# Schema_GEVE.net
KiCad netlist of a schematic drawn in Altium Designer
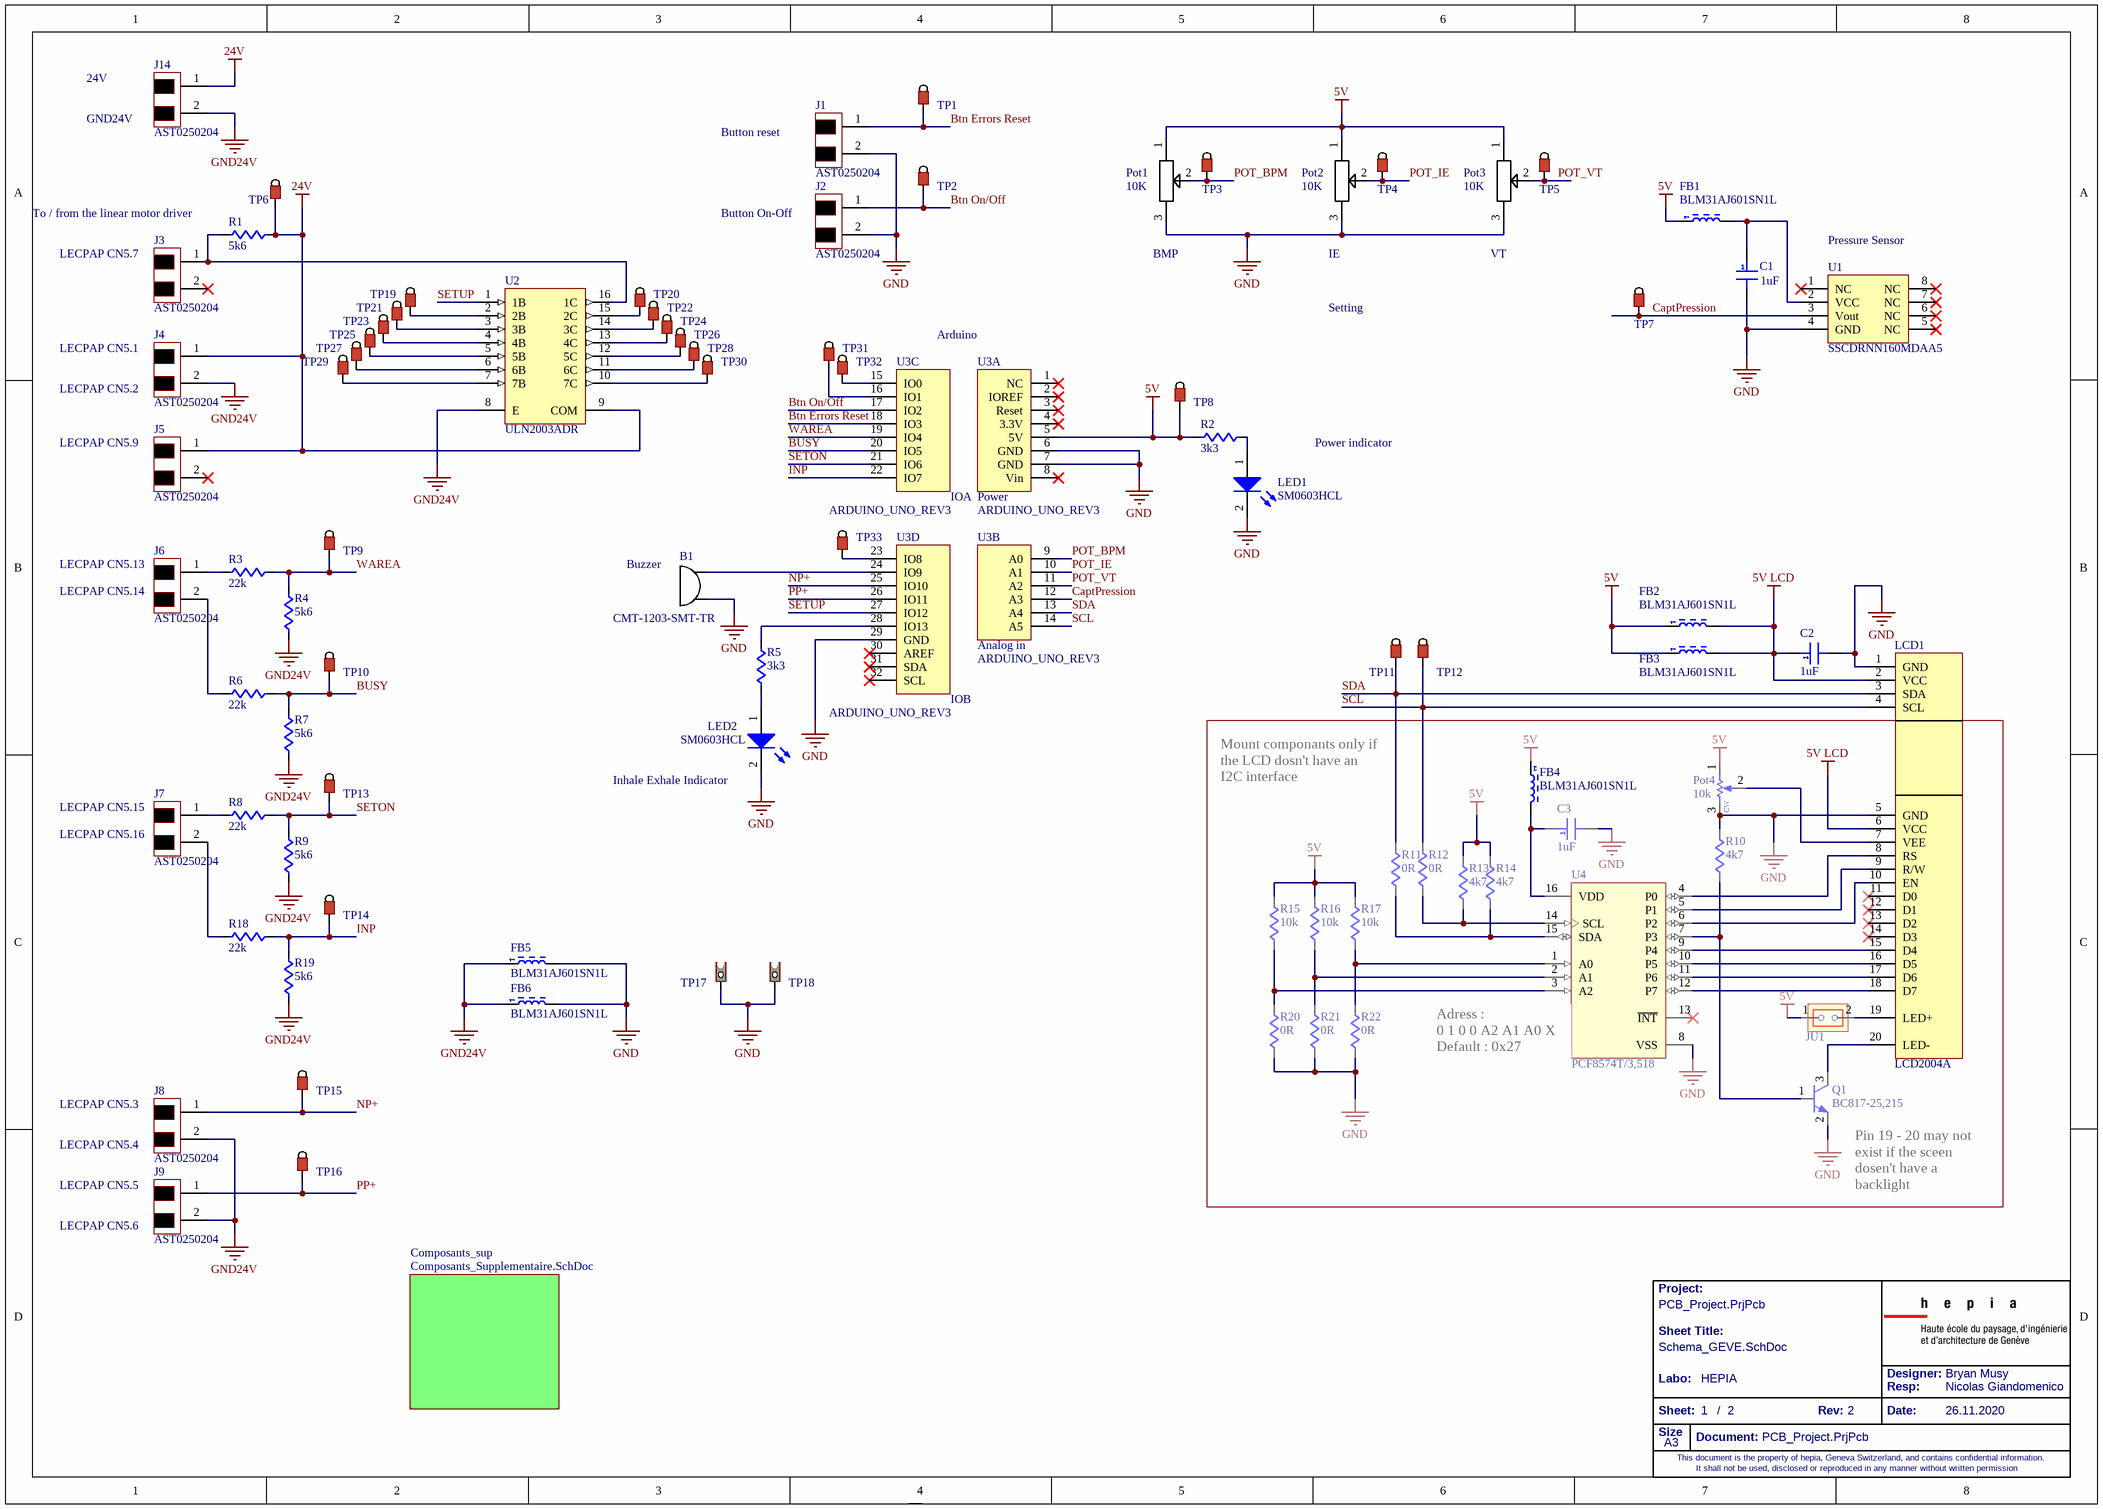
[diagram p0: Schema_GEVE.SchDoc]

(export (version "E")
  (design (tool "Eeschema 10.0.6"))
  (components
    (comp (ref "B1")
      (value "CMT-1203-SMT-TR")
      (footprint "CMT-1203-SMT-TR")
      (fields (field (name "MANUFACTURER") "CUI Devices") (field (name "DESIGNER") "B.Musy"))
      (libsource (lib "GEVE_lib") (part "CMT-1203-SMT-TR"))
    )
    (comp (ref "C1")
      (value "1uF")
      (footprint "CAP_0603H0.8")
      (description "Boite Labo 0603: Ceramic Cap, 1uF, 10%, 50V, CAP_0603H0.8")
      (fields
        (field (name "PART NUMBER") "D_CAP-64")
        (field (name "MANUFACTURER") "Murata")
        (field (name "DESIGNER") "R.Mastrocola")
      )
      (libsource (lib "Database_Altium_Hepia_Elec") (part "Cap"))
    )
    (comp (ref "C2")
      (value "1uF")
      (footprint "CAP_0603H0.8")
      (description "Boite Labo 0603: Ceramic Cap, 1uF, 10%, 50V, CAP_0603H0.8")
      (fields
        (field (name "PART NUMBER") "D_CAP-64")
        (field (name "MANUFACTURER") "Murata")
        (field (name "DESIGNER") "R.Mastrocola")
      )
      (libsource (lib "Database_Altium_Hepia_Elec") (part "Cap"))
    )
    (comp (ref "C3")
      (value "1uF")
      (footprint "CAP_0603H0.8")
      (description "Boite Labo 0603: Ceramic Cap, 1uF, 10%, 50V, CAP_0603H0.8")
      (fields
        (field (name "PART NUMBER") "D_CAP-64")
        (field (name "MANUFACTURER") "Murata")
        (field (name "DESIGNER") "R.Mastrocola")
      )
      (libsource (lib "Database_Altium_Hepia_Elec") (part "Cap"))
    )
    (comp (ref "FB1")
      (value "BLM31AJ601SN1L")
      (footprint "FERRITE_1206_1.1")
      (description "Chip Ferrite Bead, 1206, 200mA, DCRes=0.90ohm, 100MHz_Res=600ohm")
      (fields
        (field (name "PART NUMBER") "D_IND-1")
        (field (name "MANUFACTURER") "Murata")
        (field (name "DESIGNER") "FG")
      )
      (libsource (lib "Database_Altium_Hepia_Elec") (part "Ferrite"))
    )
    (comp (ref "FB2")
      (value "BLM31AJ601SN1L")
      (footprint "FERRITE_1206_1.1")
      (description "Chip Ferrite Bead, 1206, 200mA, DCRes=0.90ohm, 100MHz_Res=600ohm")
      (fields
        (field (name "PART NUMBER") "D_IND-1")
        (field (name "MANUFACTURER") "Murata")
        (field (name "DESIGNER") "FG")
      )
      (libsource (lib "Database_Altium_Hepia_Elec") (part "Ferrite"))
    )
    (comp (ref "FB3")
      (value "BLM31AJ601SN1L")
      (footprint "FERRITE_1206_1.1")
      (description "Chip Ferrite Bead, 1206, 200mA, DCRes=0.90ohm, 100MHz_Res=600ohm")
      (fields
        (field (name "PART NUMBER") "D_IND-1")
        (field (name "MANUFACTURER") "Murata")
        (field (name "DESIGNER") "FG")
      )
      (libsource (lib "Database_Altium_Hepia_Elec") (part "Ferrite"))
    )
    (comp (ref "FB4")
      (value "BLM31AJ601SN1L")
      (footprint "FERRITE_1206_1.1")
      (description "Chip Ferrite Bead, 1206, 200mA, DCRes=0.90ohm, 100MHz_Res=600ohm")
      (fields
        (field (name "PART NUMBER") "D_IND-1")
        (field (name "MANUFACTURER") "Murata")
        (field (name "DESIGNER") "FG")
      )
      (libsource (lib "Database_Altium_Hepia_Elec") (part "Ferrite"))
    )
    (comp (ref "FB5")
      (value "BLM31AJ601SN1L")
      (footprint "FERRITE_1206_1.1")
      (description "Chip Ferrite Bead, 1206, 200mA, DCRes=0.90ohm, 100MHz_Res=600ohm")
      (fields
        (field (name "PART NUMBER") "D_IND-1")
        (field (name "MANUFACTURER") "Murata")
        (field (name "DESIGNER") "FG")
      )
      (libsource (lib "Database_Altium_Hepia_Elec") (part "Ferrite"))
    )
    (comp (ref "FB6")
      (value "BLM31AJ601SN1L")
      (footprint "FERRITE_1206_1.1")
      (description "Chip Ferrite Bead, 1206, 200mA, DCRes=0.90ohm, 100MHz_Res=600ohm")
      (fields
        (field (name "PART NUMBER") "D_IND-1")
        (field (name "MANUFACTURER") "Murata")
        (field (name "DESIGNER") "FG")
      )
      (libsource (lib "Database_Altium_Hepia_Elec") (part "Ferrite"))
    )
    (comp (ref "J1")
      (value "AST0250204")
      (footprint "AST0250204")
      (fields (field (name "MANUFACTURER") "METZ Connect USA") (field (name "DESIGNER") "B.Musy"))
      (libsource (lib "GEVE_lib") (part "AST0250204"))
    )
    (comp (ref "J2")
      (value "AST0250204")
      (footprint "AST0250204")
      (fields (field (name "MANUFACTURER") "METZ Connect USA") (field (name "DESIGNER") "B.Musy"))
      (libsource (lib "GEVE_lib") (part "AST0250204"))
    )
    (comp (ref "J3")
      (value "AST0250204")
      (footprint "AST0250204")
      (fields (field (name "MANUFACTURER") "METZ Connect USA") (field (name "DESIGNER") "B.Musy"))
      (libsource (lib "GEVE_lib") (part "AST0250204"))
    )
    (comp (ref "J4")
      (value "AST0250204")
      (footprint "AST0250204")
      (fields (field (name "MANUFACTURER") "METZ Connect USA") (field (name "DESIGNER") "B.Musy"))
      (libsource (lib "GEVE_lib") (part "AST0250204"))
    )
    (comp (ref "J5")
      (value "AST0250204")
      (footprint "AST0250204")
      (fields (field (name "MANUFACTURER") "METZ Connect USA") (field (name "DESIGNER") "B.Musy"))
      (libsource (lib "GEVE_lib") (part "AST0250204"))
    )
    (comp (ref "J6")
      (value "AST0250204")
      (footprint "AST0250204")
      (fields (field (name "MANUFACTURER") "METZ Connect USA") (field (name "DESIGNER") "B.Musy"))
      (libsource (lib "GEVE_lib") (part "AST0250204"))
    )
    (comp (ref "J7")
      (value "AST0250204")
      (footprint "AST0250204")
      (fields (field (name "MANUFACTURER") "METZ Connect USA") (field (name "DESIGNER") "B.Musy"))
      (libsource (lib "GEVE_lib") (part "AST0250204"))
    )
    (comp (ref "J8")
      (value "AST0250204")
      (footprint "AST0250204")
      (fields (field (name "MANUFACTURER") "METZ Connect USA") (field (name "DESIGNER") "B.Musy"))
      (libsource (lib "GEVE_lib") (part "AST0250204"))
    )
    (comp (ref "J9")
      (value "AST0250204")
      (footprint "AST0250204")
      (fields (field (name "MANUFACTURER") "METZ Connect USA") (field (name "DESIGNER") "B.Musy"))
      (libsource (lib "GEVE_lib") (part "AST0250204"))
    )
    (comp (ref "J14")
      (value "AST0250204")
      (footprint "AST0250204")
      (description "Connecteur a levier")
      (fields (field (name "MANUFACTURER") "METZ Connect USA") (field (name "DESIGNER") "B.Musy"))
      (libsource (lib "GEVE_lib") (part "AST0250204"))
    )
    (comp (ref "JU1")
      (value "PREC002SAAN-RC")
      (footprint "Jumper_2P_P2.54")
      (description "CONN HEADER .100\" SNGL STR 2POS")
      (fields
        (field (name "PART NUMBER") "M_EME-2")
        (field (name "MANUFACTURER") "Sullins Connector Solutions")
        (field (name "DESIGNER") "R.Mastrocola")
      )
      (libsource (lib "Database_Altium_Hepia_Elec") (part "Jumper 2"))
    )
    (comp (ref "LCD1")
      (value "LCD2004A")
      (footprint "LCD2004")
      (fields (field (name "MANUFACTURER") "Geekcreit") (field (name "DESIGNER") "B.Musy"))
      (libsource (lib "GEVE_lib") (part "LCD2004A"))
    )
    (comp (ref "LED1")
      (value "SM0603HCL")
      (footprint "LED_0603-12")
      (description "LED red smd 0603 2 mA")
      (fields
        (field (name "PART NUMBER") "D_OPT-2")
        (field (name "MANUFACTURER") "Bivar")
        (field (name "DESIGNER") "FG")
      )
      (libsource (lib "Database_Altium_Hepia_Elec") (part "LED-12"))
    )
    (comp (ref "LED2")
      (value "SM0603HCL")
      (footprint "LED_0603-12")
      (description "LED red smd 0603 2 mA")
      (fields
        (field (name "PART NUMBER") "D_OPT-2")
        (field (name "MANUFACTURER") "Bivar")
        (field (name "DESIGNER") "FG")
      )
      (libsource (lib "Database_Altium_Hepia_Elec") (part "LED-12"))
    )
    (comp (ref "Pot1")
      (value "10K")
      (footprint "PCW1J-B28-BAB103L")
      (fields (field (name "MANUFACTURER") "Bourns.inc") (field (name "DESIGNER") "B.Musy"))
      (libsource (lib "GEVE_lib") (part "POT10K"))
    )
    (comp (ref "Pot2")
      (value "10K")
      (footprint "PCW1J-B28-BAB103L")
      (fields (field (name "MANUFACTURER") "Bourns.inc") (field (name "DESIGNER") "B.Musy"))
      (libsource (lib "GEVE_lib") (part "POT10K"))
    )
    (comp (ref "Pot3")
      (value "10K")
      (footprint "PCW1J-B28-BAB103L")
      (fields (field (name "MANUFACTURER") "Bourns.inc") (field (name "DESIGNER") "B.Musy"))
      (libsource (lib "GEVE_lib") (part "POT10K"))
    )
    (comp (ref "Pot4")
      (value "10k")
      (footprint "Trimpot-3313-J1")
      (description "TrimPot SMD 1 Tour 10k 3mm")
      (fields
        (field (name "PART NUMBER") "D_RES-331")
        (field (name "MANUFACTURER") "Bourns")
        (field (name "DESIGNER") "JCO")
      )
      (libsource (lib "Database_Altium_Hepia_Elec") (part "Trimmer"))
    )
    (comp (ref "Q1")
      (value "BC817-25,215")
      (footprint "SOT23-3")
      (description "Bipolar NPN, General Purpose, 45V,100MHz, 500mA")
      (fields
        (field (name "PART NUMBER") "D_TRS-9")
        (field (name "MANUFACTURER") "NXP Semi")
        (field (name "DESIGNER") "R.Mastrocola")
      )
      (libsource (lib "Database_Altium_Hepia_Elec") (part "NPN_1"))
    )
    (comp (ref "R1")
      (value "5k6")
      (footprint "RES_0603")
      (description "Thin Film Resistor, Boite Labo 0603, 5k6 1%")
      (fields
        (field (name "PART NUMBER") "D_RES-92")
        (field (name "MANUFACTURER") "Vishay")
        (field (name "DESIGNER") "R.Mastrocola")
      )
      (libsource (lib "Database_Altium_Hepia_Elec") (part "RESISTOR"))
    )
    (comp (ref "R2")
      (value "3k3")
      (footprint "RES_0603")
      (description "Thin Film Resistor, Boite Labo 0603, 3k3 1%")
      (fields
        (field (name "PART NUMBER") "D_RES-86")
        (field (name "MANUFACTURER") "Vishay")
        (field (name "DESIGNER") "R.Mastrocola")
      )
      (libsource (lib "Database_Altium_Hepia_Elec") (part "RESISTOR"))
    )
    (comp (ref "R3")
      (value "22k")
      (footprint "RES_0603")
      (description "Thin Film Resistor, Boite Labo 0603, 22k 1%")
      (fields
        (field (name "PART NUMBER") "D_RES-106")
        (field (name "MANUFACTURER") "Vishay")
        (field (name "DESIGNER") "R.Mastrocola")
      )
      (libsource (lib "Database_Altium_Hepia_Elec") (part "RESISTOR"))
    )
    (comp (ref "R4")
      (value "5k6")
      (footprint "RES_0603")
      (description "Thin Film Resistor, Boite Labo 0603, 5k6 1%")
      (fields
        (field (name "PART NUMBER") "D_RES-92")
        (field (name "MANUFACTURER") "Vishay")
        (field (name "DESIGNER") "R.Mastrocola")
      )
      (libsource (lib "Database_Altium_Hepia_Elec") (part "RESISTOR"))
    )
    (comp (ref "R5")
      (value "3k3")
      (footprint "RES_0603")
      (description "Thin Film Resistor, Boite Labo 0603, 3k3 1%")
      (fields
        (field (name "PART NUMBER") "D_RES-86")
        (field (name "MANUFACTURER") "Vishay")
        (field (name "DESIGNER") "R.Mastrocola")
      )
      (libsource (lib "Database_Altium_Hepia_Elec") (part "RESISTOR"))
    )
    (comp (ref "R6")
      (value "22k")
      (footprint "RES_0603")
      (description "Thin Film Resistor, Boite Labo 0603, 22k 1%")
      (fields
        (field (name "PART NUMBER") "D_RES-106")
        (field (name "MANUFACTURER") "Vishay")
        (field (name "DESIGNER") "R.Mastrocola")
      )
      (libsource (lib "Database_Altium_Hepia_Elec") (part "RESISTOR"))
    )
    (comp (ref "R7")
      (value "5k6")
      (footprint "RES_0603")
      (description "Thin Film Resistor, Boite Labo 0603, 5k6 1%")
      (fields
        (field (name "PART NUMBER") "D_RES-92")
        (field (name "MANUFACTURER") "Vishay")
        (field (name "DESIGNER") "R.Mastrocola")
      )
      (libsource (lib "Database_Altium_Hepia_Elec") (part "RESISTOR"))
    )
    (comp (ref "R8")
      (value "22k")
      (footprint "RES_0603")
      (description "Thin Film Resistor, Boite Labo 0603, 22k 1%")
      (fields
        (field (name "PART NUMBER") "D_RES-106")
        (field (name "MANUFACTURER") "Vishay")
        (field (name "DESIGNER") "R.Mastrocola")
      )
      (libsource (lib "Database_Altium_Hepia_Elec") (part "RESISTOR"))
    )
    (comp (ref "R9")
      (value "5k6")
      (footprint "RES_0603")
      (description "Thin Film Resistor, Boite Labo 0603, 5k6 1%")
      (fields
        (field (name "PART NUMBER") "D_RES-92")
        (field (name "MANUFACTURER") "Vishay")
        (field (name "DESIGNER") "R.Mastrocola")
      )
      (libsource (lib "Database_Altium_Hepia_Elec") (part "RESISTOR"))
    )
    (comp (ref "R10")
      (value "4k7")
      (footprint "RES_0603")
      (description "Thin Film Resistor, Boite Labo 0603, 4k7 1%")
      (fields
        (field (name "PART NUMBER") "D_RES-90")
        (field (name "MANUFACTURER") "Vishay")
        (field (name "DESIGNER") "R.Mastrocola")
      )
      (libsource (lib "Database_Altium_Hepia_Elec") (part "RESISTOR"))
    )
    (comp (ref "R11")
      (value "0R")
      (footprint "RES_0603")
      (description "Thin Film Resistor, Boite Labo 0603, Jumper 0R")
      (fields
        (field (name "PART NUMBER") "D_RES-1")
        (field (name "MANUFACTURER") "Vishay")
        (field (name "DESIGNER") "R.Mastrocola")
      )
      (libsource (lib "Database_Altium_Hepia_Elec") (part "RESISTOR"))
    )
    (comp (ref "R12")
      (value "0R")
      (footprint "RES_0603")
      (description "Thin Film Resistor, Boite Labo 0603, Jumper 0R")
      (fields
        (field (name "PART NUMBER") "D_RES-1")
        (field (name "MANUFACTURER") "Vishay")
        (field (name "DESIGNER") "R.Mastrocola")
      )
      (libsource (lib "Database_Altium_Hepia_Elec") (part "RESISTOR"))
    )
    (comp (ref "R13")
      (value "4k7")
      (footprint "RES_0603")
      (description "Thin Film Resistor, Boite Labo 0603, 4k7 1%")
      (fields
        (field (name "PART NUMBER") "D_RES-90")
        (field (name "MANUFACTURER") "Vishay")
        (field (name "DESIGNER") "R.Mastrocola")
      )
      (libsource (lib "Database_Altium_Hepia_Elec") (part "RESISTOR"))
    )
    (comp (ref "R14")
      (value "4k7")
      (footprint "RES_0603")
      (description "Thin Film Resistor, Boite Labo 0603, 4k7 1%")
      (fields
        (field (name "PART NUMBER") "D_RES-90")
        (field (name "MANUFACTURER") "Vishay")
        (field (name "DESIGNER") "R.Mastrocola")
      )
      (libsource (lib "Database_Altium_Hepia_Elec") (part "RESISTOR"))
    )
    (comp (ref "R15")
      (value "10k")
      (footprint "RES_0603")
      (description "Thin Film Resistor, Boite Labo 0603, 10k 1%")
      (fields
        (field (name "PART NUMBER") "D_RES-98")
        (field (name "MANUFACTURER") "Vishay")
        (field (name "DESIGNER") "R.Mastrocola")
      )
      (libsource (lib "Database_Altium_Hepia_Elec") (part "RESISTOR"))
    )
    (comp (ref "R16")
      (value "10k")
      (footprint "RES_0603")
      (description "Thin Film Resistor, Boite Labo 0603, 10k 1%")
      (fields
        (field (name "PART NUMBER") "D_RES-98")
        (field (name "MANUFACTURER") "Vishay")
        (field (name "DESIGNER") "R.Mastrocola")
      )
      (libsource (lib "Database_Altium_Hepia_Elec") (part "RESISTOR"))
    )
    (comp (ref "R17")
      (value "10k")
      (footprint "RES_0603")
      (description "Thin Film Resistor, Boite Labo 0603, 10k 1%")
      (fields
        (field (name "PART NUMBER") "D_RES-98")
        (field (name "MANUFACTURER") "Vishay")
        (field (name "DESIGNER") "R.Mastrocola")
      )
      (libsource (lib "Database_Altium_Hepia_Elec") (part "RESISTOR"))
    )
    (comp (ref "R18")
      (value "22k")
      (footprint "RES_0603")
      (description "Thin Film Resistor, Boite Labo 0603, 22k 1%")
      (fields
        (field (name "PART NUMBER") "D_RES-106")
        (field (name "MANUFACTURER") "Vishay")
        (field (name "DESIGNER") "R.Mastrocola")
      )
      (libsource (lib "Database_Altium_Hepia_Elec") (part "RESISTOR"))
    )
    (comp (ref "R19")
      (value "5k6")
      (footprint "RES_0603")
      (description "Thin Film Resistor, Boite Labo 0603, 5k6 1%")
      (fields
        (field (name "PART NUMBER") "D_RES-92")
        (field (name "MANUFACTURER") "Vishay")
        (field (name "DESIGNER") "R.Mastrocola")
      )
      (libsource (lib "Database_Altium_Hepia_Elec") (part "RESISTOR"))
    )
    (comp (ref "R20")
      (value "0R")
      (footprint "RES_0603")
      (description "Thin Film Resistor, Boite Labo 0603, Jumper 0R")
      (fields
        (field (name "PART NUMBER") "D_RES-1")
        (field (name "MANUFACTURER") "Vishay")
        (field (name "DESIGNER") "R.Mastrocola")
      )
      (libsource (lib "Database_Altium_Hepia_Elec") (part "RESISTOR"))
    )
    (comp (ref "R21")
      (value "0R")
      (footprint "RES_0603")
      (description "Thin Film Resistor, Boite Labo 0603, Jumper 0R")
      (fields
        (field (name "PART NUMBER") "D_RES-1")
        (field (name "MANUFACTURER") "Vishay")
        (field (name "DESIGNER") "R.Mastrocola")
      )
      (libsource (lib "Database_Altium_Hepia_Elec") (part "RESISTOR"))
    )
    (comp (ref "R22")
      (value "0R")
      (footprint "RES_0603")
      (description "Thin Film Resistor, Boite Labo 0603, Jumper 0R")
      (fields
        (field (name "PART NUMBER") "D_RES-1")
        (field (name "MANUFACTURER") "Vishay")
        (field (name "DESIGNER") "R.Mastrocola")
      )
      (libsource (lib "Database_Altium_Hepia_Elec") (part "RESISTOR"))
    )
    (comp (ref "TP1")
      (value "TP_HOOK")
      (footprint "TP_HOOK")
      (description "Test Point Hook Type")
      (fields
        (field (name "PART NUMBER") "M_TST-2")
        (field (name "MANUFACTURER") "Keystone Electronics")
        (field (name "DESIGNER") "R.Mastrocola")
      )
      (libsource (lib "Database_Altium_Hepia_Elec") (part "TP_HOOK"))
    )
    (comp (ref "TP2")
      (value "TP_HOOK")
      (footprint "TP_HOOK")
      (description "Test Point Hook Type")
      (fields
        (field (name "PART NUMBER") "M_TST-2")
        (field (name "MANUFACTURER") "Keystone Electronics")
        (field (name "DESIGNER") "R.Mastrocola")
      )
      (libsource (lib "Database_Altium_Hepia_Elec") (part "TP_HOOK"))
    )
    (comp (ref "TP3")
      (value "TP_HOOK")
      (footprint "TP_HOOK")
      (description "Test Point Hook Type")
      (fields
        (field (name "PART NUMBER") "M_TST-2")
        (field (name "MANUFACTURER") "Keystone Electronics")
        (field (name "DESIGNER") "R.Mastrocola")
      )
      (libsource (lib "Database_Altium_Hepia_Elec") (part "TP_HOOK"))
    )
    (comp (ref "TP4")
      (value "TP_HOOK")
      (footprint "TP_HOOK")
      (description "Test Point Hook Type")
      (fields
        (field (name "PART NUMBER") "M_TST-2")
        (field (name "MANUFACTURER") "Keystone Electronics")
        (field (name "DESIGNER") "R.Mastrocola")
      )
      (libsource (lib "Database_Altium_Hepia_Elec") (part "TP_HOOK"))
    )
    (comp (ref "TP5")
      (value "TP_HOOK")
      (footprint "TP_HOOK")
      (description "Test Point Hook Type")
      (fields
        (field (name "PART NUMBER") "M_TST-2")
        (field (name "MANUFACTURER") "Keystone Electronics")
        (field (name "DESIGNER") "R.Mastrocola")
      )
      (libsource (lib "Database_Altium_Hepia_Elec") (part "TP_HOOK"))
    )
    (comp (ref "TP6")
      (value "TP_HOOK")
      (footprint "TP_HOOK")
      (description "Test Point Hook Type")
      (fields
        (field (name "PART NUMBER") "M_TST-2")
        (field (name "MANUFACTURER") "Keystone Electronics")
        (field (name "DESIGNER") "R.Mastrocola")
      )
      (libsource (lib "Database_Altium_Hepia_Elec") (part "TP_HOOK"))
    )
    (comp (ref "TP7")
      (value "TP_HOOK")
      (footprint "TP_HOOK")
      (description "Test Point Hook Type")
      (fields
        (field (name "PART NUMBER") "M_TST-2")
        (field (name "MANUFACTURER") "Keystone Electronics")
        (field (name "DESIGNER") "R.Mastrocola")
      )
      (libsource (lib "Database_Altium_Hepia_Elec") (part "TP_HOOK"))
    )
    (comp (ref "TP8")
      (value "TP_HOOK")
      (footprint "TP_HOOK")
      (description "Test Point Hook Type")
      (fields
        (field (name "PART NUMBER") "M_TST-2")
        (field (name "MANUFACTURER") "Keystone Electronics")
        (field (name "DESIGNER") "R.Mastrocola")
      )
      (libsource (lib "Database_Altium_Hepia_Elec") (part "TP_HOOK"))
    )
    (comp (ref "TP9")
      (value "TP_HOOK")
      (footprint "TP_HOOK")
      (description "Test Point Hook Type")
      (fields
        (field (name "PART NUMBER") "M_TST-2")
        (field (name "MANUFACTURER") "Keystone Electronics")
        (field (name "DESIGNER") "R.Mastrocola")
      )
      (libsource (lib "Database_Altium_Hepia_Elec") (part "TP_HOOK"))
    )
    (comp (ref "TP10")
      (value "TP_HOOK")
      (footprint "TP_HOOK")
      (description "Test Point Hook Type")
      (fields
        (field (name "PART NUMBER") "M_TST-2")
        (field (name "MANUFACTURER") "Keystone Electronics")
        (field (name "DESIGNER") "R.Mastrocola")
      )
      (libsource (lib "Database_Altium_Hepia_Elec") (part "TP_HOOK"))
    )
    (comp (ref "TP11")
      (value "TP_HOOK")
      (footprint "TP_HOOK")
      (description "Test Point Hook Type")
      (fields
        (field (name "PART NUMBER") "M_TST-2")
        (field (name "MANUFACTURER") "Keystone Electronics")
        (field (name "DESIGNER") "R.Mastrocola")
      )
      (libsource (lib "Database_Altium_Hepia_Elec") (part "TP_HOOK"))
    )
    (comp (ref "TP12")
      (value "TP_HOOK")
      (footprint "TP_HOOK")
      (description "Test Point Hook Type")
      (fields
        (field (name "PART NUMBER") "M_TST-2")
        (field (name "MANUFACTURER") "Keystone Electronics")
        (field (name "DESIGNER") "R.Mastrocola")
      )
      (libsource (lib "Database_Altium_Hepia_Elec") (part "TP_HOOK"))
    )
    (comp (ref "TP13")
      (value "TP_HOOK")
      (footprint "TP_HOOK")
      (description "Test Point Hook Type")
      (fields
        (field (name "PART NUMBER") "M_TST-2")
        (field (name "MANUFACTURER") "Keystone Electronics")
        (field (name "DESIGNER") "R.Mastrocola")
      )
      (libsource (lib "Database_Altium_Hepia_Elec") (part "TP_HOOK"))
    )
    (comp (ref "TP14")
      (value "TP_HOOK")
      (footprint "TP_HOOK")
      (description "Test Point Hook Type")
      (fields
        (field (name "PART NUMBER") "M_TST-2")
        (field (name "MANUFACTURER") "Keystone Electronics")
        (field (name "DESIGNER") "R.Mastrocola")
      )
      (libsource (lib "Database_Altium_Hepia_Elec") (part "TP_HOOK"))
    )
    (comp (ref "TP15")
      (value "TP_HOOK")
      (footprint "TP_HOOK")
      (description "Test Point Hook Type")
      (fields
        (field (name "PART NUMBER") "M_TST-2")
        (field (name "MANUFACTURER") "Keystone Electronics")
        (field (name "DESIGNER") "R.Mastrocola")
      )
      (libsource (lib "Database_Altium_Hepia_Elec") (part "TP_HOOK"))
    )
    (comp (ref "TP16")
      (value "TP_HOOK")
      (footprint "TP_HOOK")
      (description "Test Point Hook Type")
      (fields
        (field (name "PART NUMBER") "M_TST-2")
        (field (name "MANUFACTURER") "Keystone Electronics")
        (field (name "DESIGNER") "R.Mastrocola")
      )
      (libsource (lib "Database_Altium_Hepia_Elec") (part "TP_HOOK"))
    )
    (comp (ref "TP17")
      (value "TP_PLATE")
      (footprint "TP_PLATE")
      (description "Test Point Plate Type (for GND)")
      (fields
        (field (name "PART NUMBER") "M_TST-3")
        (field (name "MANUFACTURER") "Keystone Electronics")
        (field (name "DESIGNER") "R.Mastrocola")
      )
      (libsource (lib "Database_Altium_Hepia_Elec") (part "TP_PLATE"))
    )
    (comp (ref "TP18")
      (value "TP_PLATE")
      (footprint "TP_PLATE")
      (description "Test Point Plate Type (for GND)")
      (fields
        (field (name "PART NUMBER") "M_TST-3")
        (field (name "MANUFACTURER") "Keystone Electronics")
        (field (name "DESIGNER") "R.Mastrocola")
      )
      (libsource (lib "Database_Altium_Hepia_Elec") (part "TP_PLATE"))
    )
    (comp (ref "TP19")
      (value "TP_HOOK")
      (footprint "TP_HOOK")
      (description "Test Point Hook Type")
      (fields
        (field (name "PART NUMBER") "M_TST-2")
        (field (name "MANUFACTURER") "Keystone Electronics")
        (field (name "DESIGNER") "R.Mastrocola")
      )
      (libsource (lib "Database_Altium_Hepia_Elec") (part "TP_HOOK"))
    )
    (comp (ref "TP20")
      (value "TP_HOOK")
      (footprint "TP_HOOK")
      (description "Test Point Hook Type")
      (fields
        (field (name "PART NUMBER") "M_TST-2")
        (field (name "MANUFACTURER") "Keystone Electronics")
        (field (name "DESIGNER") "R.Mastrocola")
      )
      (libsource (lib "Database_Altium_Hepia_Elec") (part "TP_HOOK"))
    )
    (comp (ref "TP21")
      (value "TP_HOOK")
      (footprint "TP_HOOK")
      (description "Test Point Hook Type")
      (fields
        (field (name "PART NUMBER") "M_TST-2")
        (field (name "MANUFACTURER") "Keystone Electronics")
        (field (name "DESIGNER") "R.Mastrocola")
      )
      (libsource (lib "Database_Altium_Hepia_Elec") (part "TP_HOOK"))
    )
    (comp (ref "TP22")
      (value "TP_HOOK")
      (footprint "TP_HOOK")
      (description "Test Point Hook Type")
      (fields
        (field (name "PART NUMBER") "M_TST-2")
        (field (name "MANUFACTURER") "Keystone Electronics")
        (field (name "DESIGNER") "R.Mastrocola")
      )
      (libsource (lib "Database_Altium_Hepia_Elec") (part "TP_HOOK"))
    )
    (comp (ref "TP23")
      (value "TP_HOOK")
      (footprint "TP_HOOK")
      (description "Test Point Hook Type")
      (fields
        (field (name "PART NUMBER") "M_TST-2")
        (field (name "MANUFACTURER") "Keystone Electronics")
        (field (name "DESIGNER") "R.Mastrocola")
      )
      (libsource (lib "Database_Altium_Hepia_Elec") (part "TP_HOOK"))
    )
    (comp (ref "TP24")
      (value "TP_HOOK")
      (footprint "TP_HOOK")
      (description "Test Point Hook Type")
      (fields
        (field (name "PART NUMBER") "M_TST-2")
        (field (name "MANUFACTURER") "Keystone Electronics")
        (field (name "DESIGNER") "R.Mastrocola")
      )
      (libsource (lib "Database_Altium_Hepia_Elec") (part "TP_HOOK"))
    )
    (comp (ref "TP25")
      (value "TP_HOOK")
      (footprint "TP_HOOK")
      (description "Test Point Hook Type")
      (fields
        (field (name "PART NUMBER") "M_TST-2")
        (field (name "MANUFACTURER") "Keystone Electronics")
        (field (name "DESIGNER") "R.Mastrocola")
      )
      (libsource (lib "Database_Altium_Hepia_Elec") (part "TP_HOOK"))
    )
    (comp (ref "TP26")
      (value "TP_HOOK")
      (footprint "TP_HOOK")
      (description "Test Point Hook Type")
      (fields
        (field (name "PART NUMBER") "M_TST-2")
        (field (name "MANUFACTURER") "Keystone Electronics")
        (field (name "DESIGNER") "R.Mastrocola")
      )
      (libsource (lib "Database_Altium_Hepia_Elec") (part "TP_HOOK"))
    )
    (comp (ref "TP27")
      (value "TP_HOOK")
      (footprint "TP_HOOK")
      (description "Test Point Hook Type")
      (fields
        (field (name "PART NUMBER") "M_TST-2")
        (field (name "MANUFACTURER") "Keystone Electronics")
        (field (name "DESIGNER") "R.Mastrocola")
      )
      (libsource (lib "Database_Altium_Hepia_Elec") (part "TP_HOOK"))
    )
    (comp (ref "TP28")
      (value "TP_HOOK")
      (footprint "TP_HOOK")
      (description "Test Point Hook Type")
      (fields
        (field (name "PART NUMBER") "M_TST-2")
        (field (name "MANUFACTURER") "Keystone Electronics")
        (field (name "DESIGNER") "R.Mastrocola")
      )
      (libsource (lib "Database_Altium_Hepia_Elec") (part "TP_HOOK"))
    )
    (comp (ref "TP29")
      (value "TP_HOOK")
      (footprint "TP_HOOK")
      (description "Test Point Hook Type")
      (fields
        (field (name "PART NUMBER") "M_TST-2")
        (field (name "MANUFACTURER") "Keystone Electronics")
        (field (name "DESIGNER") "R.Mastrocola")
      )
      (libsource (lib "Database_Altium_Hepia_Elec") (part "TP_HOOK"))
    )
    (comp (ref "TP30")
      (value "TP_HOOK")
      (footprint "TP_HOOK")
      (description "Test Point Hook Type")
      (fields
        (field (name "PART NUMBER") "M_TST-2")
        (field (name "MANUFACTURER") "Keystone Electronics")
        (field (name "DESIGNER") "R.Mastrocola")
      )
      (libsource (lib "Database_Altium_Hepia_Elec") (part "TP_HOOK"))
    )
    (comp (ref "TP31")
      (value "TP_HOOK")
      (footprint "TP_HOOK")
      (description "Test Point Hook Type")
      (fields
        (field (name "PART NUMBER") "M_TST-2")
        (field (name "MANUFACTURER") "Keystone Electronics")
        (field (name "DESIGNER") "R.Mastrocola")
      )
      (libsource (lib "Database_Altium_Hepia_Elec") (part "TP_HOOK"))
    )
    (comp (ref "TP32")
      (value "TP_HOOK")
      (footprint "TP_HOOK")
      (description "Test Point Hook Type")
      (fields
        (field (name "PART NUMBER") "M_TST-2")
        (field (name "MANUFACTURER") "Keystone Electronics")
        (field (name "DESIGNER") "R.Mastrocola")
      )
      (libsource (lib "Database_Altium_Hepia_Elec") (part "TP_HOOK"))
    )
    (comp (ref "TP33")
      (value "TP_HOOK")
      (footprint "TP_HOOK")
      (description "Test Point Hook Type")
      (fields
        (field (name "PART NUMBER") "M_TST-2")
        (field (name "MANUFACTURER") "Keystone Electronics")
        (field (name "DESIGNER") "R.Mastrocola")
      )
      (libsource (lib "Database_Altium_Hepia_Elec") (part "TP_HOOK"))
    )
    (comp (ref "U1")
      (value "block 2")
      (fields (field (name "DESIGNER") "B.Musy"))
      (libsource (lib "*") (part "block 2"))
    )
    (comp (ref "U2")
      (value "ULN2003ADR")
      (footprint "D0016A_M")
      (fields (field (name "MANUFACTURER") "TexasInstruments"))
      (libsource (lib "Altium Content Vault") (part "TI-ULX200X-D-16"))
    )
    (comp (ref "U3")
      (value "ARDUINO_UNO_REV3")
      (footprint "ARDUINO_A000066")
      (fields (field (name "MANUFACTURER") "Arduino") (field (name "DESIGNER") "B.Musy"))
      (libsource (lib "") (part "ARDUINOUNOREV3_1"))
    )
    (comp (ref "U4")
      (value "PCF8574T/3,518")
      (footprint "FP-SOT162-1-MFG")
      (description "IC I/O EXPANDER I2C 8B 16SOIC")
      (fields
        (field (name "MANUFACTURER") "NXP Semiconductors")
        (field (name "OCTOPART") "https://octopart.com/pcf8574t%2F3%2C518-nxp+semiconductors-10470852")
      )
      (libsource (lib "Altium Content Vault") (part "f7fde53ce59de981fb0b266a4e103eb"))
    )
  )
  (nets
    (net (code "1") (name "/BUSY") (class "Default")
      (node (ref "R6") (pin "2") (pinfunction "2_2") (pintype "passive"))
      (node (ref "R7") (pin "1") (pinfunction "1_1") (pintype "passive"))
      (node (ref "TP10") (pin "1") (pinfunction "1_1") (pintype "passive"))
      (node (ref "U3") (pin "20") (pinfunction "IO5_20") (pintype "passive"))
    )
    (net (code "2") (name "/Btn Errors Reset") (class "Default")
      (node (ref "J1") (pin "1") (pinfunction "1_1") (pintype "passive"))
      (node (ref "TP1") (pin "1") (pinfunction "1_1") (pintype "passive"))
      (node (ref "U3") (pin "18") (pinfunction "IO3_18") (pintype "passive"))
    )
    (net (code "3") (name "/Btn On{slash}Off") (class "Default")
      (node (ref "J2") (pin "1") (pinfunction "1_1") (pintype "passive"))
      (node (ref "TP2") (pin "1") (pinfunction "1_1") (pintype "passive"))
      (node (ref "U3") (pin "17") (pinfunction "IO2_17") (pintype "passive"))
    )
    (net (code "4") (name "/CaptPression") (class "Default")
      (node (ref "TP7") (pin "1") (pinfunction "1_1") (pintype "passive"))
      (node (ref "U1") (pin "3") (pinfunction "Vout_3") (pintype "passive"))
      (node (ref "U3") (pin "12") (pinfunction "A3_12") (pintype "passive"))
    )
    (net (code "5") (name "/INP") (class "Default")
      (node (ref "R18") (pin "2") (pinfunction "2_2") (pintype "passive"))
      (node (ref "R19") (pin "1") (pinfunction "1_1") (pintype "passive"))
      (node (ref "TP14") (pin "1") (pinfunction "1_1") (pintype "passive"))
      (node (ref "U3") (pin "22") (pinfunction "IO7_22") (pintype "passive"))
    )
    (net (code "6") (name "/NP+") (class "Default")
      (node (ref "J8") (pin "1") (pinfunction "1_1") (pintype "passive"))
      (node (ref "TP15") (pin "1") (pinfunction "1_1") (pintype "passive"))
      (node (ref "U3") (pin "25") (pinfunction "IO10_25") (pintype "passive"))
    )
    (net (code "7") (name "/POT_BPM") (class "Default")
      (node (ref "Pot1") (pin "2") (pinfunction "2_2") (pintype "passive"))
      (node (ref "TP3") (pin "1") (pinfunction "1_1") (pintype "passive"))
      (node (ref "U3") (pin "9") (pinfunction "A0_9") (pintype "passive"))
    )
    (net (code "8") (name "/POT_IE") (class "Default")
      (node (ref "Pot2") (pin "2") (pinfunction "2_2") (pintype "passive"))
      (node (ref "TP4") (pin "1") (pinfunction "1_1") (pintype "passive"))
      (node (ref "U3") (pin "10") (pinfunction "A1_10") (pintype "passive"))
    )
    (net (code "9") (name "/POT_VT") (class "Default")
      (node (ref "Pot3") (pin "2") (pinfunction "2_2") (pintype "passive"))
      (node (ref "TP5") (pin "1") (pinfunction "1_1") (pintype "passive"))
      (node (ref "U3") (pin "11") (pinfunction "A2_11") (pintype "passive"))
    )
    (net (code "10") (name "/PP+") (class "Default")
      (node (ref "J9") (pin "1") (pinfunction "1_1") (pintype "passive"))
      (node (ref "TP16") (pin "1") (pinfunction "1_1") (pintype "passive"))
      (node (ref "U3") (pin "26") (pinfunction "IO11_26") (pintype "passive"))
    )
    (net (code "11") (name "/SCL") (class "Default")
      (node (ref "LCD1") (pin "4") (pinfunction "SCL_4") (pintype "passive"))
      (node (ref "R12") (pin "1") (pinfunction "1_1") (pintype "passive"))
      (node (ref "TP12") (pin "1") (pinfunction "1_1") (pintype "passive"))
      (node (ref "U3") (pin "14") (pinfunction "A5_14") (pintype "passive"))
    )
    (net (code "12") (name "/SDA") (class "Default")
      (node (ref "LCD1") (pin "3") (pinfunction "SDA_3") (pintype "passive"))
      (node (ref "R11") (pin "1") (pinfunction "1_1") (pintype "passive"))
      (node (ref "TP11") (pin "1") (pinfunction "1_1") (pintype "passive"))
      (node (ref "U3") (pin "13") (pinfunction "A4_13") (pintype "passive"))
    )
    (net (code "13") (name "/SETON") (class "Default")
      (node (ref "R8") (pin "2") (pinfunction "2_2") (pintype "passive"))
      (node (ref "R9") (pin "1") (pinfunction "1_1") (pintype "passive"))
      (node (ref "TP13") (pin "1") (pinfunction "1_1") (pintype "passive"))
      (node (ref "U3") (pin "21") (pinfunction "IO6_21") (pintype "passive"))
    )
    (net (code "14") (name "/SETUP") (class "Default")
      (node (ref "U2") (pin "1") (pinfunction "1B_1") (pintype "input"))
      (node (ref "U3") (pin "27") (pinfunction "IO12_27") (pintype "passive"))
    )
    (net (code "15") (name "/WAREA") (class "Default")
      (node (ref "R3") (pin "2") (pinfunction "2_2") (pintype "passive"))
      (node (ref "R4") (pin "1") (pinfunction "1_1") (pintype "passive"))
      (node (ref "TP9") (pin "1") (pinfunction "1_1") (pintype "passive"))
      (node (ref "U3") (pin "19") (pinfunction "IO4_19") (pintype "passive"))
    )
    (net (code "16") (name "5V") (class "Default")
      (node (ref "FB1") (pin "1") (pinfunction "1_1") (pintype "passive"))
      (node (ref "FB2") (pin "1") (pinfunction "1_1") (pintype "passive"))
      (node (ref "FB3") (pin "1") (pinfunction "1_1") (pintype "passive"))
      (node (ref "FB4") (pin "1") (pinfunction "1_1") (pintype "passive"))
      (node (ref "JU1") (pin "1") (pinfunction "1_1") (pintype "passive"))
      (node (ref "Pot1") (pin "1") (pinfunction "1_1") (pintype "passive"))
      (node (ref "Pot2") (pin "1") (pinfunction "1_1") (pintype "passive"))
      (node (ref "Pot3") (pin "1") (pinfunction "1_1") (pintype "passive"))
      (node (ref "Pot4") (pin "1") (pinfunction "CCW_1") (pintype "passive"))
      (node (ref "R13") (pin "1") (pinfunction "1_1") (pintype "passive"))
      (node (ref "R14") (pin "1") (pinfunction "1_1") (pintype "passive"))
      (node (ref "R15") (pin "1") (pinfunction "1_1") (pintype "passive"))
      (node (ref "R16") (pin "1") (pinfunction "1_1") (pintype "passive"))
      (node (ref "R17") (pin "1") (pinfunction "1_1") (pintype "passive"))
      (node (ref "R2") (pin "1") (pinfunction "1_1") (pintype "passive"))
      (node (ref "TP8") (pin "1") (pinfunction "1_1") (pintype "passive"))
      (node (ref "U3") (pin "5") (pinfunction "5V_5") (pintype "passive"))
    )
    (net (code "17") (name "5V LCD") (class "Default")
      (node (ref "C2") (pin "1") (pinfunction "1_1") (pintype "passive"))
      (node (ref "FB2") (pin "2") (pinfunction "2_2") (pintype "passive"))
      (node (ref "FB3") (pin "2") (pinfunction "2_2") (pintype "passive"))
      (node (ref "LCD1") (pin "2") (pinfunction "VCC_2") (pintype "passive"))
      (node (ref "LCD1") (pin "6") (pinfunction "VCC_6") (pintype "passive"))
    )
    (net (code "18") (name "24V") (class "Default")
      (node (ref "J14") (pin "1") (pinfunction "1_1") (pintype "passive"))
      (node (ref "J4") (pin "1") (pinfunction "1_1") (pintype "passive"))
      (node (ref "J5") (pin "1") (pinfunction "1_1") (pintype "passive"))
      (node (ref "R1") (pin "2") (pinfunction "2_2") (pintype "passive"))
      (node (ref "TP6") (pin "1") (pinfunction "1_1") (pintype "passive"))
      (node (ref "U2") (pin "9") (pinfunction "COM_9") (pintype "passive"))
    )
    (net (code "19") (name "GND") (class "Default")
      (node (ref "B1") (pin "1") (pinfunction "0_1") (pintype "passive"))
      (node (ref "C1") (pin "2") (pinfunction "2_2") (pintype "passive"))
      (node (ref "C2") (pin "2") (pinfunction "2_2") (pintype "passive"))
      (node (ref "C3") (pin "2") (pinfunction "2_2") (pintype "passive"))
      (node (ref "FB5") (pin "2") (pinfunction "2_2") (pintype "passive"))
      (node (ref "FB6") (pin "2") (pinfunction "2_2") (pintype "passive"))
      (node (ref "J1") (pin "2") (pinfunction "2_2") (pintype "passive"))
      (node (ref "J2") (pin "2") (pinfunction "2_2") (pintype "passive"))
      (node (ref "LCD1") (pin "1") (pinfunction "GND_1") (pintype "passive"))
      (node (ref "LCD1") (pin "5") (pinfunction "GND_5") (pintype "passive"))
      (node (ref "LED1") (pin "2") (pinfunction "K_2") (pintype "passive"))
      (node (ref "LED2") (pin "2") (pinfunction "K_2") (pintype "passive"))
      (node (ref "Pot1") (pin "3") (pinfunction "3_3") (pintype "passive"))
      (node (ref "Pot2") (pin "3") (pinfunction "3_3") (pintype "passive"))
      (node (ref "Pot3") (pin "3") (pinfunction "3_3") (pintype "passive"))
      (node (ref "Pot4") (pin "3") (pinfunction "CW_3") (pintype "passive"))
      (node (ref "Q1") (pin "2") (pinfunction "E_2") (pintype "passive"))
      (node (ref "R10") (pin "1") (pinfunction "1_1") (pintype "passive"))
      (node (ref "R20") (pin "2") (pinfunction "2_2") (pintype "passive"))
      (node (ref "R21") (pin "2") (pinfunction "2_2") (pintype "passive"))
      (node (ref "R22") (pin "2") (pinfunction "2_2") (pintype "passive"))
      (node (ref "TP17") (pin "1") (pinfunction "1_1") (pintype "passive"))
      (node (ref "TP18") (pin "1") (pinfunction "1_1") (pintype "passive"))
      (node (ref "U1") (pin "4") (pinfunction "GND_4") (pintype "passive"))
      (node (ref "U3") (pin "29") (pinfunction "GND_29") (pintype "passive"))
      (node (ref "U3") (pin "6") (pinfunction "GND_6") (pintype "passive"))
      (node (ref "U3") (pin "7") (pinfunction "GND_7") (pintype "passive"))
      (node (ref "U4") (pin "8") (pinfunction "VSS_8") (pintype "power_in"))
    )
    (net (code "20") (name "GND24V") (class "Default")
      (node (ref "FB5") (pin "1") (pinfunction "1_1") (pintype "passive"))
      (node (ref "FB6") (pin "1") (pinfunction "1_1") (pintype "passive"))
      (node (ref "J14") (pin "2") (pinfunction "2_2") (pintype "passive"))
      (node (ref "J4") (pin "2") (pinfunction "2_2") (pintype "passive"))
      (node (ref "J8") (pin "2") (pinfunction "2_2") (pintype "passive"))
      (node (ref "J9") (pin "2") (pinfunction "2_2") (pintype "passive"))
      (node (ref "R19") (pin "2") (pinfunction "2_2") (pintype "passive"))
      (node (ref "R4") (pin "2") (pinfunction "2_2") (pintype "passive"))
      (node (ref "R7") (pin "2") (pinfunction "2_2") (pintype "passive"))
      (node (ref "R9") (pin "2") (pinfunction "2_2") (pintype "passive"))
      (node (ref "U2") (pin "8") (pinfunction "E_8") (pintype "passive"))
    )
    (net (code "21") (name "Net-(J6-Pad1)") (class "Default")
      (node (ref "J6") (pin "1") (pinfunction "1_1") (pintype "passive"))
      (node (ref "R3") (pin "1") (pinfunction "1_1") (pintype "passive"))
    )
    (net (code "22") (name "Net-(J6-Pad2)") (class "Default")
      (node (ref "J6") (pin "2") (pinfunction "2_2") (pintype "passive"))
      (node (ref "R6") (pin "1") (pinfunction "1_1") (pintype "passive"))
    )
    (net (code "23") (name "Net-(J7-Pad1)") (class "Default")
      (node (ref "J7") (pin "1") (pinfunction "1_1") (pintype "passive"))
      (node (ref "R8") (pin "1") (pinfunction "1_1") (pintype "passive"))
    )
    (net (code "24") (name "Net-(J7-Pad2)") (class "Default")
      (node (ref "J7") (pin "2") (pinfunction "2_2") (pintype "passive"))
      (node (ref "R18") (pin "1") (pinfunction "1_1") (pintype "passive"))
    )
    (net (code "25") (name "Net-(LCD1-D4)") (class "Default")
      (node (ref "LCD1") (pin "15") (pinfunction "D4_15") (pintype "passive"))
      (node (ref "U4") (pin "9") (pinfunction "P4_9") (pintype "bidirectional"))
    )
    (net (code "26") (name "Net-(LCD1-D5)") (class "Default")
      (node (ref "LCD1") (pin "16") (pinfunction "D5_16") (pintype "passive"))
      (node (ref "U4") (pin "10") (pinfunction "P5_10") (pintype "bidirectional"))
    )
    (net (code "27") (name "Net-(LCD1-D6)") (class "Default")
      (node (ref "LCD1") (pin "17") (pinfunction "D6_17") (pintype "passive"))
      (node (ref "U4") (pin "11") (pinfunction "P6_11") (pintype "bidirectional"))
    )
    (net (code "28") (name "Net-(LCD1-D7)") (class "Default")
      (node (ref "LCD1") (pin "18") (pinfunction "D7_18") (pintype "passive"))
      (node (ref "U4") (pin "12") (pinfunction "P7_12") (pintype "bidirectional"))
    )
    (net (code "29") (name "Net-(LCD1-EN)") (class "Default")
      (node (ref "LCD1") (pin "10") (pinfunction "EN_10") (pintype "passive"))
      (node (ref "U4") (pin "6") (pinfunction "P2_6") (pintype "bidirectional"))
    )
    (net (code "30") (name "Net-(LCD1-LED+)") (class "Default")
      (node (ref "JU1") (pin "2") (pinfunction "2_2") (pintype "passive"))
      (node (ref "LCD1") (pin "19") (pinfunction "LED+_19") (pintype "passive"))
    )
    (net (code "31") (name "Net-(LCD1-LED-)") (class "Default")
      (node (ref "LCD1") (pin "20") (pinfunction "LED-_20") (pintype "passive"))
      (node (ref "Q1") (pin "3") (pinfunction "C_3") (pintype "passive"))
    )
    (net (code "32") (name "Net-(LCD1-RS)") (class "Default")
      (node (ref "LCD1") (pin "8") (pinfunction "RS_8") (pintype "passive"))
      (node (ref "U4") (pin "4") (pinfunction "P0_4") (pintype "bidirectional"))
    )
    (net (code "33") (name "Net-(LCD1-R{slash}W)") (class "Default")
      (node (ref "LCD1") (pin "9") (pinfunction "R/W_9") (pintype "passive"))
      (node (ref "U4") (pin "5") (pinfunction "P1_5") (pintype "bidirectional"))
    )
    (net (code "34") (name "Net-(LCD1-VEE)") (class "Default")
      (node (ref "LCD1") (pin "7") (pinfunction "VEE_7") (pintype "passive"))
      (node (ref "Pot4") (pin "2") (pinfunction "WIPER_2") (pintype "passive"))
    )
    (net (code "35") (name "Net-(LED1-A)") (class "Default")
      (node (ref "LED1") (pin "1") (pinfunction "A_1") (pintype "passive"))
      (node (ref "R2") (pin "2") (pinfunction "2_2") (pintype "passive"))
    )
    (net (code "36") (name "Net-(LED2-A)") (class "Default")
      (node (ref "LED2") (pin "1") (pinfunction "A_1") (pintype "passive"))
      (node (ref "R5") (pin "2") (pinfunction "2_2") (pintype "passive"))
    )
    (net (code "37") (name "Net-(Q1-B)") (class "Default")
      (node (ref "Q1") (pin "1") (pinfunction "B_1") (pintype "passive"))
      (node (ref "R10") (pin "2") (pinfunction "2_2") (pintype "passive"))
      (node (ref "U4") (pin "7") (pinfunction "P3_7") (pintype "bidirectional"))
    )
    (net (code "38") (name "Net-(U1-VCC)") (class "Default")
      (node (ref "C1") (pin "1") (pinfunction "1_1") (pintype "passive"))
      (node (ref "FB1") (pin "2") (pinfunction "2_2") (pintype "passive"))
      (node (ref "U1") (pin "2") (pinfunction "VCC_2") (pintype "passive"))
    )
    (net (code "39") (name "Net-(U2-1C)") (class "Default")
      (node (ref "J3") (pin "1") (pinfunction "1_1") (pintype "passive"))
      (node (ref "R1") (pin "1") (pinfunction "1_1") (pintype "passive"))
      (node (ref "U2") (pin "16") (pinfunction "1C_16") (pintype "output"))
    )
    (net (code "40") (name "Net-(U2-2B)") (class "Default")
      (node (ref "TP19") (pin "1") (pinfunction "1_1") (pintype "passive"))
      (node (ref "U2") (pin "2") (pinfunction "2B_2") (pintype "input"))
    )
    (net (code "41") (name "Net-(U2-2C)") (class "Default")
      (node (ref "TP20") (pin "1") (pinfunction "1_1") (pintype "passive"))
      (node (ref "U2") (pin "15") (pinfunction "2C_15") (pintype "output"))
    )
    (net (code "42") (name "Net-(U2-3B)") (class "Default")
      (node (ref "TP21") (pin "1") (pinfunction "1_1") (pintype "passive"))
      (node (ref "U2") (pin "3") (pinfunction "3B_3") (pintype "input"))
    )
    (net (code "43") (name "Net-(U2-3C)") (class "Default")
      (node (ref "TP22") (pin "1") (pinfunction "1_1") (pintype "passive"))
      (node (ref "U2") (pin "14") (pinfunction "3C_14") (pintype "output"))
    )
    (net (code "44") (name "Net-(U2-4B)") (class "Default")
      (node (ref "TP23") (pin "1") (pinfunction "1_1") (pintype "passive"))
      (node (ref "U2") (pin "4") (pinfunction "4B_4") (pintype "input"))
    )
    (net (code "45") (name "Net-(U2-4C)") (class "Default")
      (node (ref "TP24") (pin "1") (pinfunction "1_1") (pintype "passive"))
      (node (ref "U2") (pin "13") (pinfunction "4C_13") (pintype "output"))
    )
    (net (code "46") (name "Net-(U2-5B)") (class "Default")
      (node (ref "TP25") (pin "1") (pinfunction "1_1") (pintype "passive"))
      (node (ref "U2") (pin "5") (pinfunction "5B_5") (pintype "input"))
    )
    (net (code "47") (name "Net-(U2-5C)") (class "Default")
      (node (ref "TP26") (pin "1") (pinfunction "1_1") (pintype "passive"))
      (node (ref "U2") (pin "12") (pinfunction "5C_12") (pintype "output"))
    )
    (net (code "48") (name "Net-(U2-6B)") (class "Default")
      (node (ref "TP27") (pin "1") (pinfunction "1_1") (pintype "passive"))
      (node (ref "U2") (pin "6") (pinfunction "6B_6") (pintype "input"))
    )
    (net (code "49") (name "Net-(U2-6C)") (class "Default")
      (node (ref "TP28") (pin "1") (pinfunction "1_1") (pintype "passive"))
      (node (ref "U2") (pin "11") (pinfunction "6C_11") (pintype "output"))
    )
    (net (code "50") (name "Net-(U2-7B)") (class "Default")
      (node (ref "TP29") (pin "1") (pinfunction "1_1") (pintype "passive"))
      (node (ref "U2") (pin "7") (pinfunction "7B_7") (pintype "input"))
    )
    (net (code "51") (name "Net-(U2-7C)") (class "Default")
      (node (ref "TP30") (pin "1") (pinfunction "1_1") (pintype "passive"))
      (node (ref "U2") (pin "10") (pinfunction "7C_10") (pintype "output"))
    )
    (net (code "52") (name "Net-(U3C-IO0)") (class "Default")
      (node (ref "TP32") (pin "1") (pinfunction "1_1") (pintype "passive"))
      (node (ref "U3") (pin "15") (pinfunction "IO0_15") (pintype "passive"))
    )
    (net (code "53") (name "Net-(U3C-IO1)") (class "Default")
      (node (ref "TP31") (pin "1") (pinfunction "1_1") (pintype "passive"))
      (node (ref "U3") (pin "16") (pinfunction "IO1_16") (pintype "passive"))
    )
    (net (code "54") (name "Net-(U3D-IO8)") (class "Default")
      (node (ref "TP33") (pin "1") (pinfunction "1_1") (pintype "passive"))
      (node (ref "U3") (pin "23") (pinfunction "IO8_23") (pintype "passive"))
    )
    (net (code "55") (name "Net-(U3D-IO9)") (class "Default")
      (node (ref "B1") (pin "2") (pintype "passive"))
      (node (ref "U3") (pin "24") (pinfunction "IO9_24") (pintype "passive"))
    )
    (net (code "56") (name "Net-(U3D-IO13)") (class "Default")
      (node (ref "R5") (pin "1") (pinfunction "1_1") (pintype "passive"))
      (node (ref "U3") (pin "28") (pinfunction "IO13_28") (pintype "passive"))
    )
    (net (code "57") (name "Net-(U4-A0)") (class "Default")
      (node (ref "R17") (pin "2") (pinfunction "2_2") (pintype "passive"))
      (node (ref "R22") (pin "1") (pinfunction "1_1") (pintype "passive"))
      (node (ref "U4") (pin "1") (pinfunction "A0_1") (pintype "input"))
    )
    (net (code "58") (name "Net-(U4-A1)") (class "Default")
      (node (ref "R16") (pin "2") (pinfunction "2_2") (pintype "passive"))
      (node (ref "R21") (pin "1") (pinfunction "1_1") (pintype "passive"))
      (node (ref "U4") (pin "2") (pinfunction "A1_2") (pintype "input"))
    )
    (net (code "59") (name "Net-(U4-A2)") (class "Default")
      (node (ref "R15") (pin "2") (pinfunction "2_2") (pintype "passive"))
      (node (ref "R20") (pin "1") (pinfunction "1_1") (pintype "passive"))
      (node (ref "U4") (pin "3") (pinfunction "A2_3") (pintype "input"))
    )
    (net (code "60") (name "Net-(U4-SCL)") (class "Default")
      (node (ref "R12") (pin "2") (pinfunction "2_2") (pintype "passive"))
      (node (ref "R13") (pin "2") (pinfunction "2_2") (pintype "passive"))
      (node (ref "U4") (pin "14") (pinfunction "SCL_14") (pintype "input"))
    )
    (net (code "61") (name "Net-(U4-SDA)") (class "Default")
      (node (ref "R11") (pin "2") (pinfunction "2_2") (pintype "passive"))
      (node (ref "R14") (pin "2") (pinfunction "2_2") (pintype "passive"))
      (node (ref "U4") (pin "15") (pinfunction "SDA_15") (pintype "bidirectional"))
    )
    (net (code "62") (name "Net-(U4-VDD)") (class "Default")
      (node (ref "C3") (pin "1") (pinfunction "1_1") (pintype "passive"))
      (node (ref "FB4") (pin "2") (pinfunction "2_2") (pintype "passive"))
      (node (ref "U4") (pin "16") (pinfunction "VDD_16") (pintype "power_in"))
    )
    (net (code "63") (name "unconnected-(J3-Pad2)") (class "Default")
      (node (ref "J3") (pin "2") (pinfunction "2_2") (pintype "passive+no_connect"))
    )
    (net (code "64") (name "unconnected-(J5-Pad2)") (class "Default")
      (node (ref "J5") (pin "2") (pinfunction "2_2") (pintype "passive+no_connect"))
    )
    (net (code "65") (name "unconnected-(LCD1-D0-Pad11)") (class "Default")
      (node (ref "LCD1") (pin "11") (pinfunction "D0_11") (pintype "passive+no_connect"))
    )
    (net (code "66") (name "unconnected-(LCD1-D1-Pad12)") (class "Default")
      (node (ref "LCD1") (pin "12") (pinfunction "D1_12") (pintype "passive+no_connect"))
    )
    (net (code "67") (name "unconnected-(LCD1-D2-Pad13)") (class "Default")
      (node (ref "LCD1") (pin "13") (pinfunction "D2_13") (pintype "passive+no_connect"))
    )
    (net (code "68") (name "unconnected-(LCD1-D3-Pad14)") (class "Default")
      (node (ref "LCD1") (pin "14") (pinfunction "D3_14") (pintype "passive+no_connect"))
    )
    (net (code "69") (name "unconnected-(U1-NC-Pad1)") (class "Default")
      (node (ref "U1") (pin "1") (pinfunction "NC_1") (pintype "passive+no_connect"))
    )
    (net (code "70") (name "unconnected-(U1-NC-Pad5)") (class "Default")
      (node (ref "U1") (pin "5") (pinfunction "NC_5") (pintype "passive+no_connect"))
    )
    (net (code "71") (name "unconnected-(U1-NC-Pad6)") (class "Default")
      (node (ref "U1") (pin "6") (pinfunction "NC_6") (pintype "passive+no_connect"))
    )
    (net (code "72") (name "unconnected-(U1-NC-Pad7)") (class "Default")
      (node (ref "U1") (pin "7") (pinfunction "NC_7") (pintype "passive+no_connect"))
    )
    (net (code "73") (name "unconnected-(U1-NC-Pad8)") (class "Default")
      (node (ref "U1") (pin "8") (pinfunction "NC_8") (pintype "passive+no_connect"))
    )
    (net (code "74") (name "unconnected-(U3A-3.3V-Pad4)") (class "Default")
      (node (ref "U3") (pin "4") (pinfunction "3.3V_4") (pintype "passive+no_connect"))
    )
    (net (code "75") (name "unconnected-(U3A-IOREF-Pad2)") (class "Default")
      (node (ref "U3") (pin "2") (pinfunction "IOREF_2") (pintype "passive+no_connect"))
    )
    (net (code "76") (name "unconnected-(U3A-NC-Pad1)") (class "Default")
      (node (ref "U3") (pin "1") (pinfunction "NC_1") (pintype "passive+no_connect"))
    )
    (net (code "77") (name "unconnected-(U3A-Reset-Pad3)") (class "Default")
      (node (ref "U3") (pin "3") (pinfunction "Reset_3") (pintype "passive+no_connect"))
    )
    (net (code "78") (name "unconnected-(U3A-Vin-Pad8)") (class "Default")
      (node (ref "U3") (pin "8") (pinfunction "Vin_8") (pintype "passive+no_connect"))
    )
    (net (code "79") (name "unconnected-(U3D-AREF-Pad30)") (class "Default")
      (node (ref "U3") (pin "30") (pinfunction "AREF_30") (pintype "passive+no_connect"))
    )
    (net (code "80") (name "unconnected-(U3D-SCL-Pad32)") (class "Default")
      (node (ref "U3") (pin "32") (pinfunction "SCL_32") (pintype "passive+no_connect"))
    )
    (net (code "81") (name "unconnected-(U3D-SDA-Pad31)") (class "Default")
      (node (ref "U3") (pin "31") (pinfunction "SDA_31") (pintype "passive+no_connect"))
    )
    (net (code "82") (name "unconnected-(U4-~{INT}-Pad13)") (class "Default")
      (node (ref "U4") (pin "13") (pinfunction "~{INT}_13") (pintype "open_collector+no_connect"))
    )
  )
)
